# Apollo4-BluePlus-Module_rev_a-v33.net
KiCad netlist of a schematic drawn in EAGLE
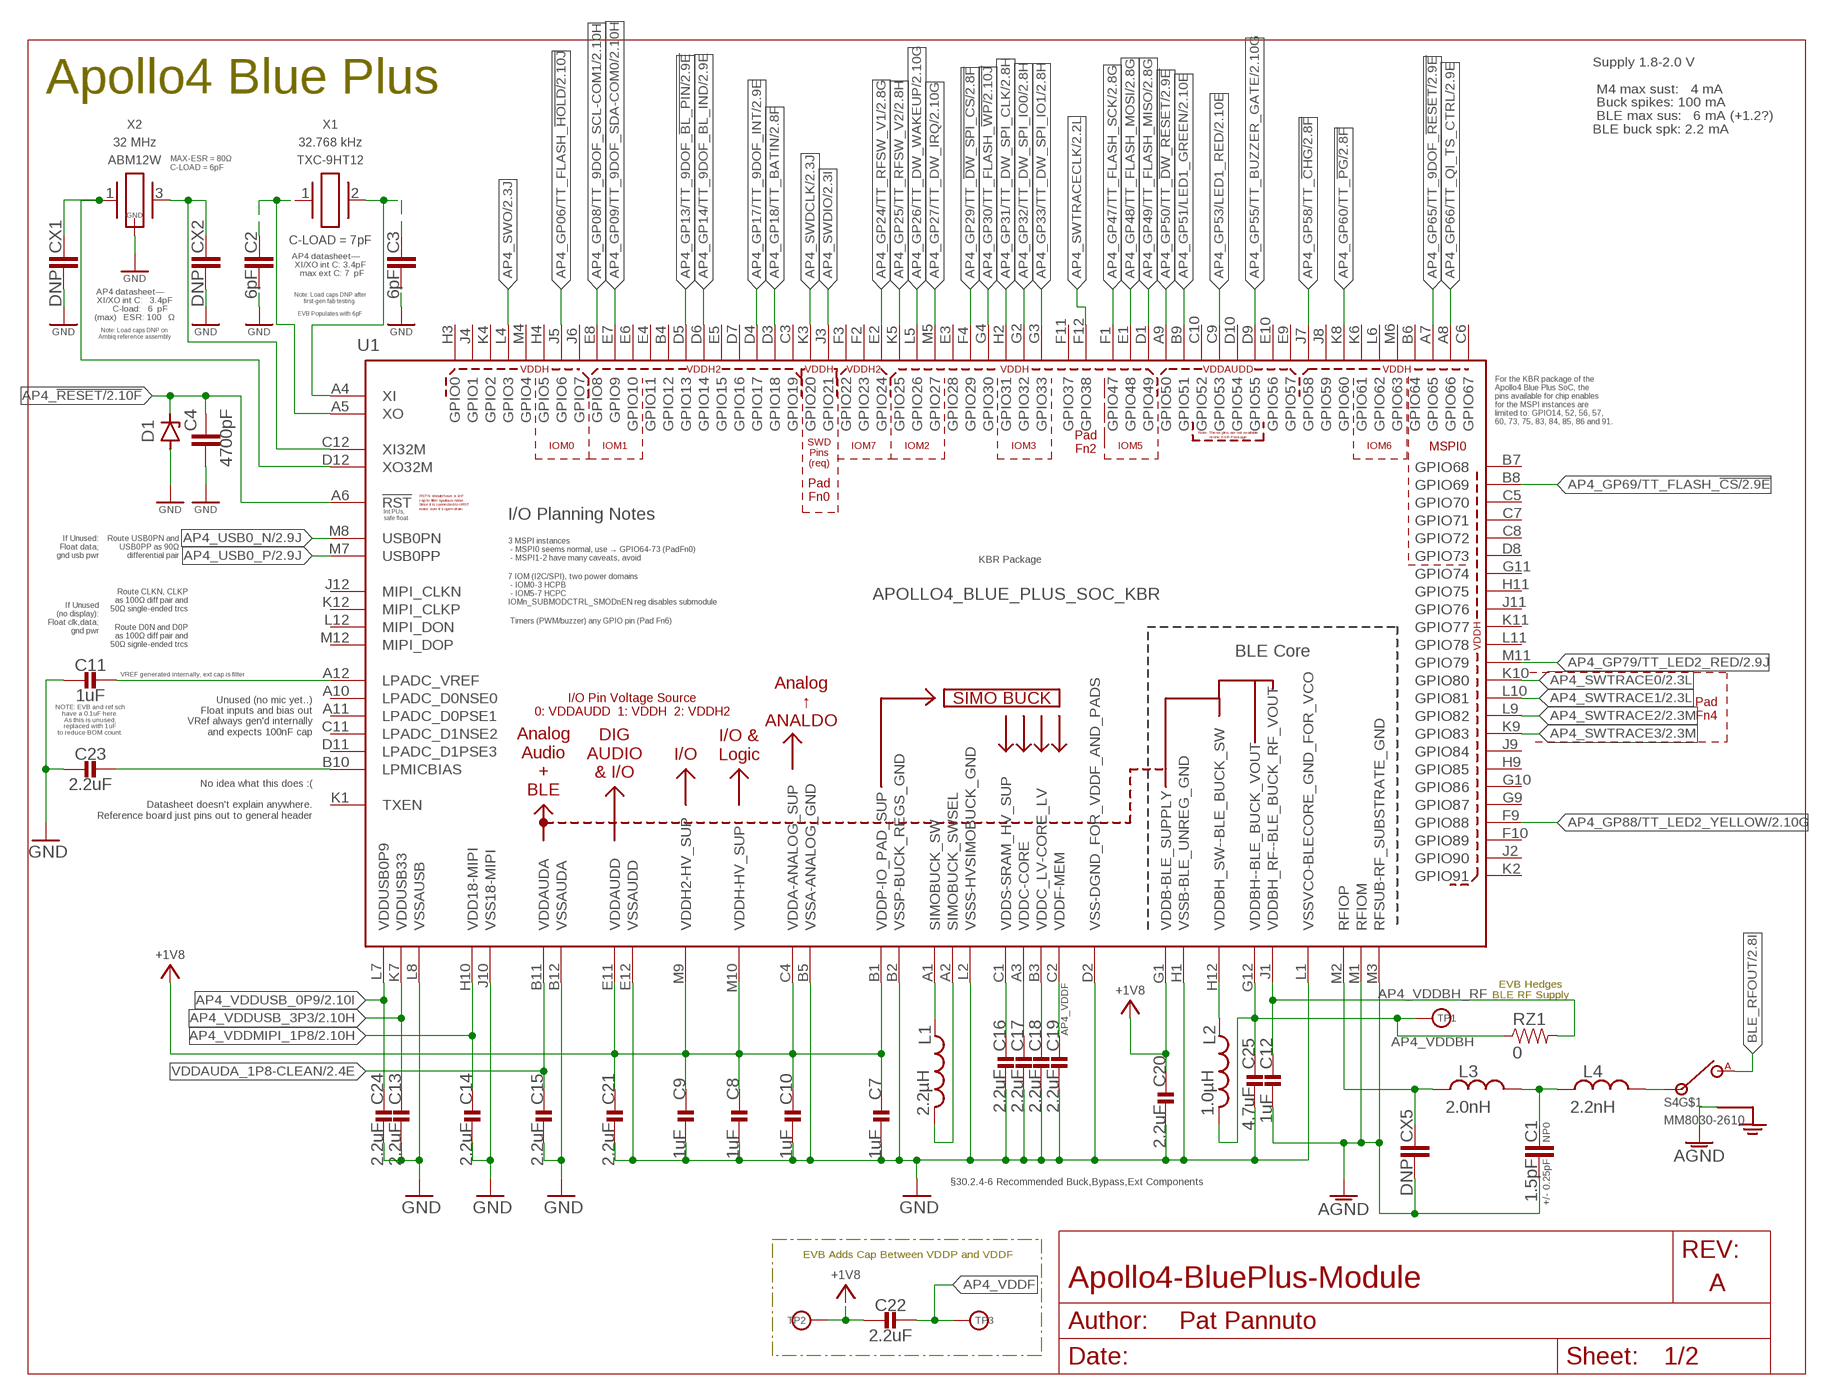
[diagram p0: schematic, sheet 1]
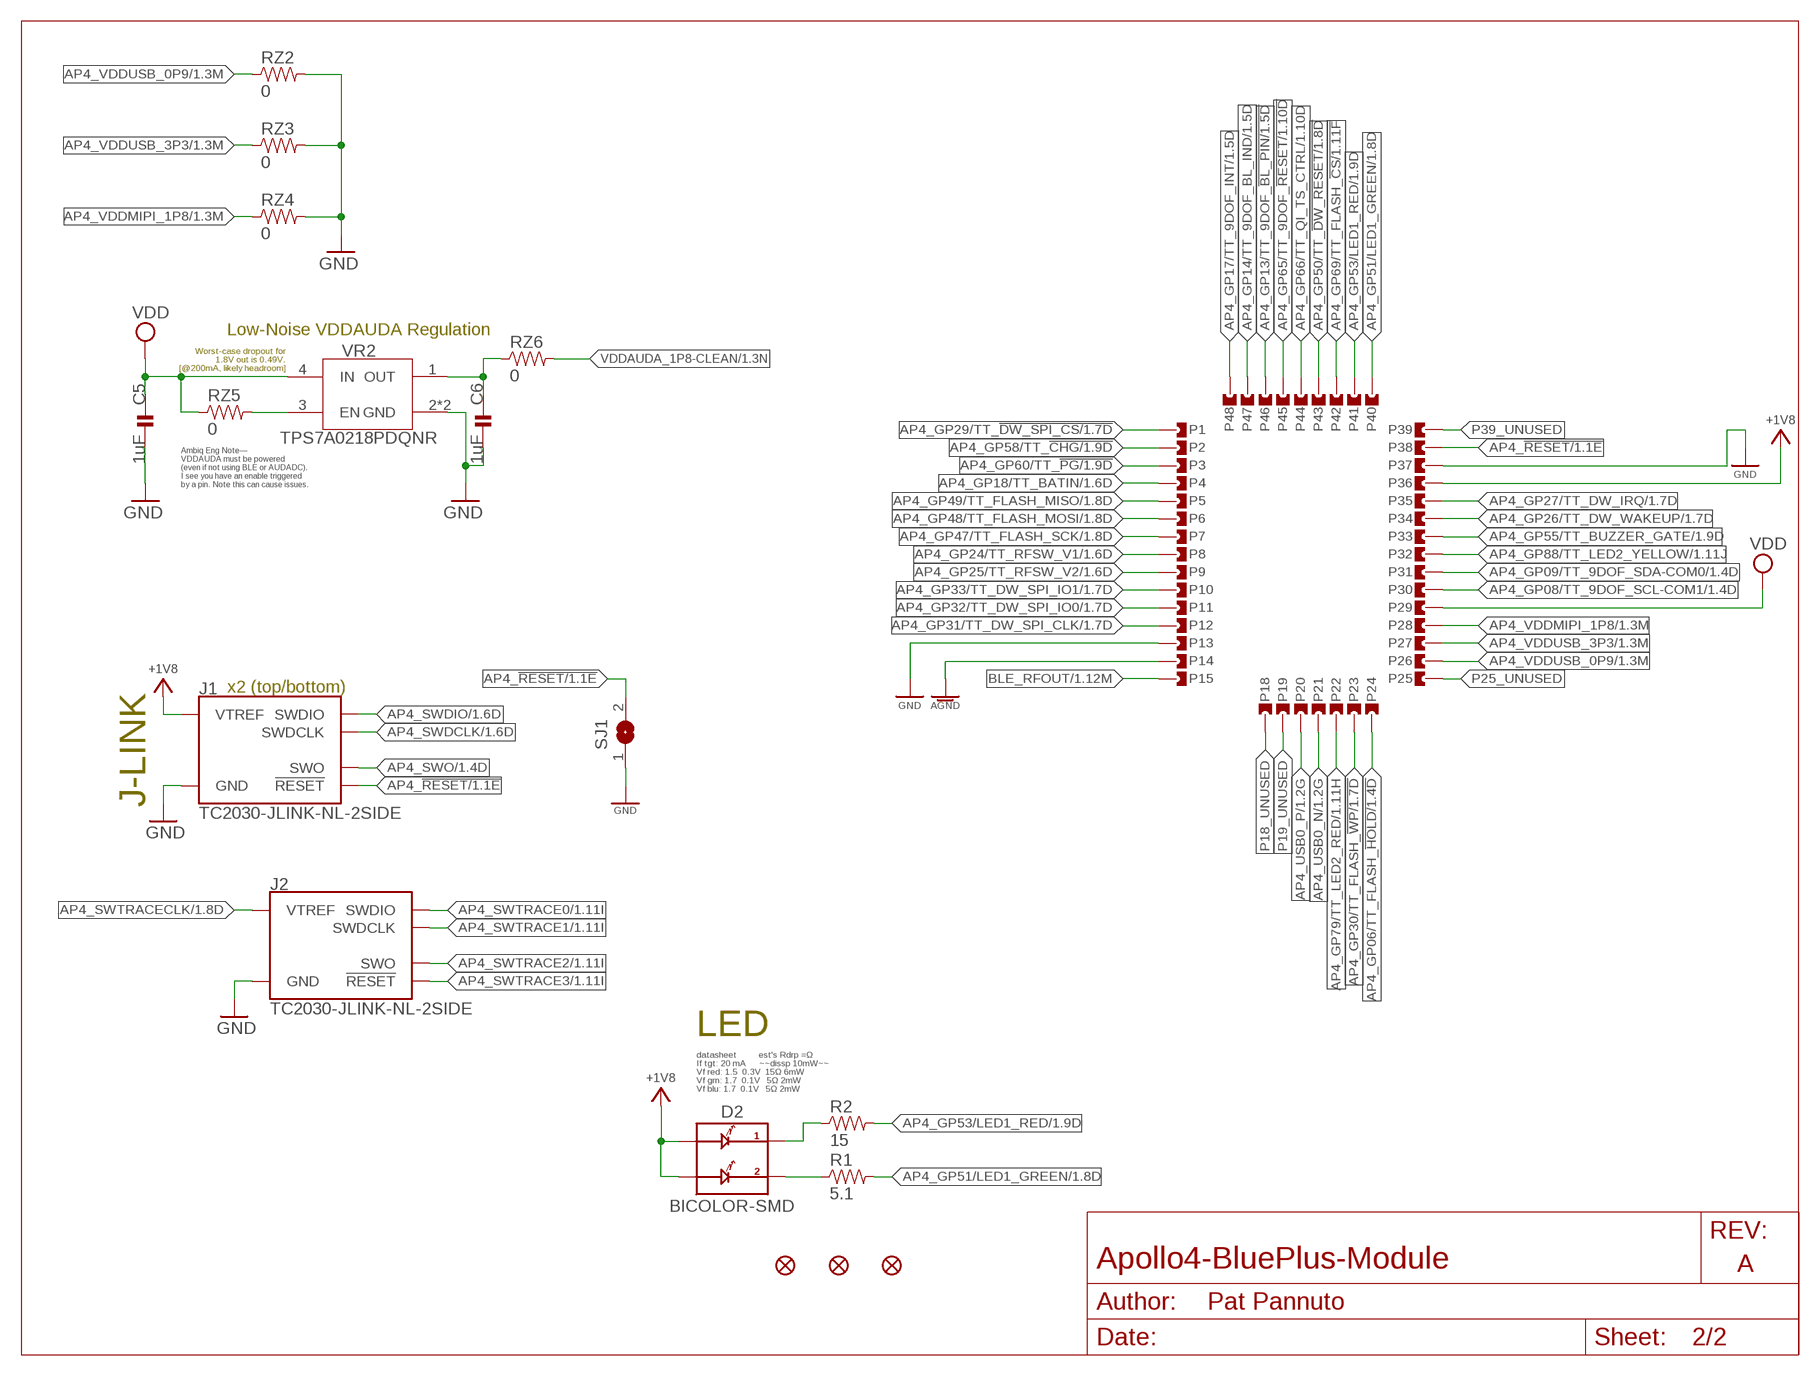
[diagram p1: schematic, sheet 2]

(export (version "E")
  (design (tool "Eeschema 10.0.6"))
  (components
    (comp (ref "C1")
      (value "1.5pF")
      (footprint "eagle-import:CAPC1005X60")
      (description "CAP CER 1.5PF 50V C0G/NP0 0402")
      (fields
        (field (name "MANUFACTURER") "KEMET")
        (field (name "MPN") "C0402C159C5GAC7867")
        (field (name "TEMPCOEFF") "NP0")
        (field (name "TOLERANCE") "+/- 0.25pF")
      )
      (libsource (lib "eagle-import") (part "CCHIP-0402(1005-METRIC)_"))
    )
    (comp (ref "C2")
      (value "6pF")
      (footprint "eagle-import:CAPC1005X60")
      (fields (field (name "MANUFACTURER") "Murata") (field (name "MPN") "GCM1555C1H6R0BA16D"))
      (libsource (lib "eagle-import") (part "CCHIP-0402(1005-METRIC)_"))
    )
    (comp (ref "C3")
      (value "6pF")
      (footprint "eagle-import:CAPC1005X60")
      (fields (field (name "MANUFACTURER") "Murata") (field (name "MPN") "GCM1555C1H6R0BA16D"))
      (libsource (lib "eagle-import") (part "CCHIP-0402(1005-METRIC)_"))
    )
    (comp (ref "C4")
      (value "4700pF")
      (footprint "eagle-import:CAPC1005X60")
      (fields (field (name "MPN") "KGM05AR71E472KH"))
      (libsource (lib "eagle-import") (part "CCHIP-0402(1005-METRIC)_"))
    )
    (comp (ref "C7")
      (value "1uF")
      (footprint "eagle-import:0201_CAP")
      (fields (field (name "MANUFACTURER") "Murata") (field (name "MPN") "GRM033R61A105ME44D"))
      (libsource (lib "eagle-import") (part "passives_20904581_CAPACITOR0201_CAP"))
    )
    (comp (ref "C8")
      (value "1uF")
      (footprint "eagle-import:0201_CAP")
      (fields (field (name "MANUFACTURER") "Murata") (field (name "MPN") "GRM033R61A105ME44D"))
      (libsource (lib "eagle-import") (part "passives_20904581_CAPACITOR0201_CAP"))
    )
    (comp (ref "C9")
      (value "1uF")
      (footprint "eagle-import:0201_CAP")
      (fields (field (name "MANUFACTURER") "Murata") (field (name "MPN") "GRM033R61A105ME44D"))
      (libsource (lib "eagle-import") (part "passives_20904581_CAPACITOR0201_CAP"))
    )
    (comp (ref "C10")
      (value "1uF")
      (footprint "eagle-import:0201_CAP")
      (fields (field (name "MANUFACTURER") "Murata") (field (name "MPN") "GRM033R61A105ME44D"))
      (libsource (lib "eagle-import") (part "passives_20904581_CAPACITOR0201_CAP"))
    )
    (comp (ref "C11")
      (value "1uF")
      (footprint "eagle-import:0201_CAP")
      (fields (field (name "MANUFACTURER") "MURATA") (field (name "MPN") "GRM033R61A105ME44D"))
      (libsource (lib "eagle-import") (part "passives_20904581_CAPACITOR0201_CAP"))
    )
    (comp (ref "C12")
      (value "1uF")
      (footprint "eagle-import:0201_CAP")
      (fields (field (name "MANUFACTURER") "Murata") (field (name "MPN") "GRM033R61A105ME44D"))
      (libsource (lib "eagle-import") (part "passives_20904581_CAPACITOR0201_CAP"))
    )
    (comp (ref "C13")
      (value "2.2uF")
      (footprint "eagle-import:0201_CAP")
      (fields (field (name "MANUFACTURER") "Murata") (field (name "MPN") "GRM033R61A225KE47D"))
      (libsource (lib "eagle-import") (part "passives_20904581_CAPACITOR0201_CAP"))
    )
    (comp (ref "C14")
      (value "2.2uF")
      (footprint "eagle-import:0201_CAP")
      (fields (field (name "MANUFACTURER") "Murata") (field (name "MPN") "GRM033R61A225KE47D"))
      (libsource (lib "eagle-import") (part "passives_20904581_CAPACITOR0201_CAP"))
    )
    (comp (ref "C15")
      (value "2.2uF")
      (footprint "eagle-import:0201_CAP")
      (fields (field (name "MANUFACTURER") "Murata") (field (name "MPN") "GRM033R61A225KE47D"))
      (libsource (lib "eagle-import") (part "passives_20904581_CAPACITOR0201_CAP"))
    )
    (comp (ref "C16")
      (value "2.2uF")
      (footprint "eagle-import:0201_CAP")
      (fields (field (name "MANUFACTURER") "Murata") (field (name "MPN") "GRM033R61A225KE47D"))
      (libsource (lib "eagle-import") (part "passives_20904581_CAPACITOR0201_CAP"))
    )
    (comp (ref "C17")
      (value "2.2uF")
      (footprint "eagle-import:0201_CAP")
      (fields (field (name "MANUFACTURER") "Murata") (field (name "MPN") "GRM033R61A225KE47D"))
      (libsource (lib "eagle-import") (part "passives_20904581_CAPACITOR0201_CAP"))
    )
    (comp (ref "C18")
      (value "2.2uF")
      (footprint "eagle-import:0201_CAP")
      (fields (field (name "MANUFACTURER") "Murata") (field (name "MPN") "GRM033R61A225KE47D"))
      (libsource (lib "eagle-import") (part "passives_20904581_CAPACITOR0201_CAP"))
    )
    (comp (ref "C19")
      (value "2.2uF")
      (footprint "eagle-import:0201_CAP")
      (fields (field (name "MANUFACTURER") "Murata") (field (name "MPN") "GRM033R61A225KE47D"))
      (libsource (lib "eagle-import") (part "passives_20904581_CAPACITOR0201_CAP"))
    )
    (comp (ref "C20")
      (value "2.2uF")
      (footprint "eagle-import:0201_CAP")
      (fields (field (name "MANUFACTURER") "Murata") (field (name "MPN") "GRM033R61A225KE47D"))
      (libsource (lib "eagle-import") (part "passives_20904581_CAPACITOR0201_CAP"))
    )
    (comp (ref "C21")
      (value "2.2uF")
      (footprint "eagle-import:0201_CAP")
      (fields (field (name "MANUFACTURER") "Murata") (field (name "MPN") "GRM033R61A225KE47D"))
      (libsource (lib "eagle-import") (part "passives_20904581_CAPACITOR0201_CAP"))
    )
    (comp (ref "C22")
      (value "2.2uF")
      (footprint "eagle-import:0201_CAP")
      (fields (field (name "MANUFACTURER") "Murata") (field (name "MPN") "GRM033R61A225KE47D"))
      (libsource (lib "eagle-import") (part "passives_20904581_CAPACITOR0201_CAP"))
    )
    (comp (ref "C23")
      (value "2.2uF")
      (footprint "eagle-import:0201_CAP")
      (fields (field (name "MANUFACTURER") "Murata") (field (name "MPN") "GRM033R61A225KE47D"))
      (libsource (lib "eagle-import") (part "passives_20904581_CAPACITOR0201_CAP"))
    )
    (comp (ref "C24")
      (value "2.2uF")
      (footprint "eagle-import:0201_CAP")
      (fields (field (name "MANUFACTURER") "Murata") (field (name "MPN") "GRM033R61A225KE47D"))
      (libsource (lib "eagle-import") (part "passives_20904581_CAPACITOR0201_CAP"))
    )
    (comp (ref "C25")
      (value "4.7uF")
      (footprint "eagle-import:0402_CAP")
      (fields (field (name "MPN") "CL05A475MP5NRNC"))
      (libsource (lib "eagle-import") (part "CAPACITOR0402_CAP"))
    )
    (comp (ref "CX1")
      (value "DNP")
      (footprint "eagle-import:CAPC1005X60")
      (libsource (lib "eagle-import") (part "CCHIP-0402(1005-METRIC)_"))
    )
    (comp (ref "CX2")
      (value "DNP")
      (footprint "eagle-import:CAPC1005X60")
      (libsource (lib "eagle-import") (part "CCHIP-0402(1005-METRIC)_"))
    )
    (comp (ref "CX5")
      (value "DNP")
      (footprint "eagle-import:CAPC1005X60")
      (libsource (lib "eagle-import") (part "CCHIP-0402(1005-METRIC)_"))
    )
    (comp (ref "D1")
      (value "ZENER")
      (footprint "eagle-import:SODFL1608X70")
      (description "DIODE TVS 5.5V STANDOFF 8V BREAKDOWN SC79")
      (fields (field (name "MANUFACTURER") "NXP SEMICONDUCTOR") (field (name "MPN") "PESD5V0X1UB,135"))
      (libsource (lib "eagle-import") (part "ZENERSODFL(1608-METRIC)_"))
    )
    (comp (ref "L1")
      (value "2.2µH")
      (footprint "eagle-import:0805_CAP")
      (fields (field (name "MANUFACTURER") "Murata") (field (name "MPN") "DFE201210U-2R2M=P2"))
      (libsource (lib "eagle-import") (part "INDUCTOR0805"))
    )
    (comp (ref "L2")
      (value "1.0µH")
      (footprint "eagle-import:0603_CAP")
      (fields (field (name "MANUFACTURER") "Murata") (field (name "MPN") "DFE18SAN1R0ME0L"))
      (libsource (lib "eagle-import") (part "INDUCTOR0603"))
    )
    (comp (ref "L3")
      (value "2.0nH")
      (footprint "eagle-import:INDC1006X60N")
      (description "FIXED IND 2.0NH0.1NH SMD")
      (fields
        (field (name "MANUFACTURER") "Central Technologies")
        (field (name "MPN") "CTTF0402F-2N0B")
        (field (name "TOLERANCE") "+/- 0.1 nH")
      )
      (libsource (lib "eagle-import") (part "LCHIP-0402(1006-METRIC)_"))
    )
    (comp (ref "L4")
      (value "2.2nH")
      (footprint "eagle-import:INDC1006X60N")
      (description "FIXED IND 2.2NH0.1NH SMD")
      (fields
        (field (name "MANUFACTURER") "Central Technologies")
        (field (name "MPN") "CTTF0402F-2N2B")
        (field (name "TOLERANCE") "+/- 0.1 nH")
      )
      (libsource (lib "eagle-import") (part "LCHIP-0402(1006-METRIC)_"))
    )
    (comp (ref "RZ1")
      (value "0")
      (footprint "eagle-import:0402_RES")
      (fields (field (name "MPN") "RMCF0402ZT0R00"))
      (libsource (lib "eagle-import") (part "RESISTOR0402_RES"))
    )
    (comp (ref "S4")
      (value "MM8030-2610")
      (footprint "eagle-import:MM8030-2610")
      (fields (field (name "MANUFACTURER") "Murata"))
      (libsource (lib "eagle-import") (part "MM8030-2610"))
    )
    (comp (ref "TP1")
      (value "VDDBH")
      (footprint "eagle-import:PAD.03X.03")
      (libsource (lib "eagle-import") (part "TEST-POINT"))
    )
    (comp (ref "TP2")
      (value "VDDP")
      (footprint "eagle-import:PAD.03X.03")
      (libsource (lib "eagle-import") (part "TEST-POINT"))
    )
    (comp (ref "TP3")
      (value "VDDF")
      (footprint "eagle-import:PAD.03X.03")
      (libsource (lib "eagle-import") (part "TEST-POINT"))
    )
    (comp (ref "U1")
      (value "APOLLO4_BLUE_PLUS_SOC_KBR")
      (footprint "eagle-import:APOLLO4_BLUE_SOC_BGA")
      (libsource (lib "eagle-import") (part "APOLLO4_BLUE_PLUS_SOC_KBR"))
    )
    (comp (ref "X1")
      (value "TXC-9HT12")
      (footprint "eagle-import:TXC-9HT12")
      (fields
        (field (name "C-LOAD") "7pF")
        (field (name "FREQUENCY") "32.768 kHz")
        (field (name "MANUFACTURER") "TXC Corp")
        (field (name "MPN") "9HT12-32.768KDZY-T")
      )
      (libsource (lib "eagle-import") (part "TXC-9HT12"))
    )
    (comp (ref "X2")
      (value "ABM12W")
      (footprint "eagle-import:ABM12W")
      (fields
        (field (name "C-LOAD") "6pF")
        (field (name "FREQUENCY") "32 MHz")
        (field (name "MANUFACTURER") "Abracon")
        (field (name "MAX-ESR") "80Ω")
        (field (name "MPN") "ABM12W-32.0000MHZ-6-D1X-T3")
      )
      (libsource (lib "eagle-import") (part "ABM12W"))
    )
    (comp (ref "C5")
      (value "1uF")
      (footprint "eagle-import:0201_CAP")
      (fields (field (name "MANUFACTURER") "Murata") (field (name "MPN") "GRM033R61A105ME44D"))
      (libsource (lib "eagle-import") (part "passives_20904581_CAPACITOR0201_CAP"))
    )
    (comp (ref "C6")
      (value "1uF")
      (footprint "eagle-import:0201_CAP")
      (fields (field (name "MANUFACTURER") "Murata") (field (name "MPN") "GRM033R61A105ME44D"))
      (libsource (lib "eagle-import") (part "passives_20904581_CAPACITOR0201_CAP"))
    )
    (comp (ref "D2")
      (value "BICOLOR-SMD")
      (footprint "eagle-import:LED-0606")
      (fields (field (name "MPN") "MCL0606FRD1GR1T"))
      (libsource (lib "eagle-import") (part "BICOLOR-SMD"))
    )
    (comp (ref "FD1")
      (value "FIDUCIALUFIDUCIAL")
      (footprint "eagle-import:FIDUCIAL-MICRO")
      (libsource (lib "eagle-import") (part "FIDUCIALUFIDUCIAL"))
    )
    (comp (ref "FD2")
      (value "FIDUCIALUFIDUCIAL")
      (footprint "eagle-import:FIDUCIAL-MICRO")
      (libsource (lib "eagle-import") (part "FIDUCIALUFIDUCIAL"))
    )
    (comp (ref "FD3")
      (value "FIDUCIALUFIDUCIAL")
      (footprint "eagle-import:FIDUCIAL-MICRO")
      (libsource (lib "eagle-import") (part "FIDUCIALUFIDUCIAL"))
    )
    (comp (ref "J1")
      (value "TC2030-JLINK-NL-2SIDE")
      (footprint "eagle-import:TC2030-IDC-NL-2SIDE")
      (libsource (lib "eagle-import") (part "TC2030-JLINK-NL-2SIDE"))
    )
    (comp (ref "J2")
      (value "TC2030-JLINK-NL-2SIDE")
      (footprint "eagle-import:TC2030-IDC-NL-2SIDE")
      (libsource (lib "eagle-import") (part "TC2030-JLINK-NL-2SIDE"))
    )
    (comp (ref "P1")
      (value "CASTELLATION4L")
      (footprint "eagle-import:CASTELLATION-0.55MM_DRILL-4L")
      (libsource (lib "eagle-import") (part "CASTELLATION4L"))
    )
    (comp (ref "P2")
      (value "CASTELLATION4L")
      (footprint "eagle-import:CASTELLATION-0.55MM_DRILL-4L")
      (libsource (lib "eagle-import") (part "CASTELLATION4L"))
    )
    (comp (ref "P3")
      (value "CASTELLATION4L")
      (footprint "eagle-import:CASTELLATION-0.55MM_DRILL-4L")
      (libsource (lib "eagle-import") (part "CASTELLATION4L"))
    )
    (comp (ref "P4")
      (value "CASTELLATION4L")
      (footprint "eagle-import:CASTELLATION-0.55MM_DRILL-4L")
      (libsource (lib "eagle-import") (part "CASTELLATION4L"))
    )
    (comp (ref "P5")
      (value "CASTELLATION4L")
      (footprint "eagle-import:CASTELLATION-0.55MM_DRILL-4L")
      (libsource (lib "eagle-import") (part "CASTELLATION4L"))
    )
    (comp (ref "P6")
      (value "CASTELLATION4L")
      (footprint "eagle-import:CASTELLATION-0.55MM_DRILL-4L")
      (libsource (lib "eagle-import") (part "CASTELLATION4L"))
    )
    (comp (ref "P7")
      (value "CASTELLATION4L")
      (footprint "eagle-import:CASTELLATION-0.55MM_DRILL-4L")
      (libsource (lib "eagle-import") (part "CASTELLATION4L"))
    )
    (comp (ref "P8")
      (value "CASTELLATION4L")
      (footprint "eagle-import:CASTELLATION-0.55MM_DRILL-4L")
      (libsource (lib "eagle-import") (part "CASTELLATION4L"))
    )
    (comp (ref "P9")
      (value "CASTELLATION4L")
      (footprint "eagle-import:CASTELLATION-0.55MM_DRILL-4L")
      (libsource (lib "eagle-import") (part "CASTELLATION4L"))
    )
    (comp (ref "P10")
      (value "CASTELLATION4L")
      (footprint "eagle-import:CASTELLATION-0.55MM_DRILL-4L")
      (libsource (lib "eagle-import") (part "CASTELLATION4L"))
    )
    (comp (ref "P11")
      (value "CASTELLATION4L")
      (footprint "eagle-import:CASTELLATION-0.55MM_DRILL-4L")
      (libsource (lib "eagle-import") (part "CASTELLATION4L"))
    )
    (comp (ref "P12")
      (value "CASTELLATION4L")
      (footprint "eagle-import:CASTELLATION-0.55MM_DRILL-4L")
      (libsource (lib "eagle-import") (part "CASTELLATION4L"))
    )
    (comp (ref "P13")
      (value "CASTELLATION4L")
      (footprint "eagle-import:CASTELLATION-0.55MM_DRILL-4L")
      (libsource (lib "eagle-import") (part "CASTELLATION4L"))
    )
    (comp (ref "P14")
      (value "CASTELLATION4L")
      (footprint "eagle-import:CASTELLATION-0.55MM_DRILL-4L")
      (libsource (lib "eagle-import") (part "CASTELLATION4L"))
    )
    (comp (ref "P15")
      (value "CASTELLATION4L")
      (footprint "eagle-import:CASTELLATION-0.55MM_DRILL-4L")
      (libsource (lib "eagle-import") (part "CASTELLATION4L"))
    )
    (comp (ref "P18")
      (value "CASTELLATION4L")
      (footprint "eagle-import:CASTELLATION-0.55MM_DRILL-4L")
      (libsource (lib "eagle-import") (part "CASTELLATION4L"))
    )
    (comp (ref "P19")
      (value "CASTELLATION4L")
      (footprint "eagle-import:CASTELLATION-0.55MM_DRILL-4L")
      (libsource (lib "eagle-import") (part "CASTELLATION4L"))
    )
    (comp (ref "P20")
      (value "CASTELLATION4L")
      (footprint "eagle-import:CASTELLATION-0.55MM_DRILL-4L")
      (libsource (lib "eagle-import") (part "CASTELLATION4L"))
    )
    (comp (ref "P21")
      (value "CASTELLATION4L")
      (footprint "eagle-import:CASTELLATION-0.55MM_DRILL-4L")
      (libsource (lib "eagle-import") (part "CASTELLATION4L"))
    )
    (comp (ref "P22")
      (value "CASTELLATION4L")
      (footprint "eagle-import:CASTELLATION-0.55MM_DRILL-4L")
      (libsource (lib "eagle-import") (part "CASTELLATION4L"))
    )
    (comp (ref "P23")
      (value "CASTELLATION4L")
      (footprint "eagle-import:CASTELLATION-0.55MM_DRILL-4L")
      (libsource (lib "eagle-import") (part "CASTELLATION4L"))
    )
    (comp (ref "P24")
      (value "CASTELLATION4L")
      (footprint "eagle-import:CASTELLATION-0.55MM_DRILL-4L")
      (libsource (lib "eagle-import") (part "CASTELLATION4L"))
    )
    (comp (ref "P25")
      (value "CASTELLATION4L")
      (footprint "eagle-import:CASTELLATION-0.55MM_DRILL-4L")
      (libsource (lib "eagle-import") (part "CASTELLATION4L"))
    )
    (comp (ref "P26")
      (value "CASTELLATION4L")
      (footprint "eagle-import:CASTELLATION-0.55MM_DRILL-4L")
      (libsource (lib "eagle-import") (part "CASTELLATION4L"))
    )
    (comp (ref "P27")
      (value "CASTELLATION4L")
      (footprint "eagle-import:CASTELLATION-0.55MM_DRILL-4L")
      (libsource (lib "eagle-import") (part "CASTELLATION4L"))
    )
    (comp (ref "P28")
      (value "CASTELLATION4L")
      (footprint "eagle-import:CASTELLATION-0.55MM_DRILL-4L")
      (libsource (lib "eagle-import") (part "CASTELLATION4L"))
    )
    (comp (ref "P29")
      (value "CASTELLATION4L")
      (footprint "eagle-import:CASTELLATION-0.55MM_DRILL-4L")
      (libsource (lib "eagle-import") (part "CASTELLATION4L"))
    )
    (comp (ref "P30")
      (value "CASTELLATION4L")
      (footprint "eagle-import:CASTELLATION-0.55MM_DRILL-4L")
      (libsource (lib "eagle-import") (part "CASTELLATION4L"))
    )
    (comp (ref "P31")
      (value "CASTELLATION4L")
      (footprint "eagle-import:CASTELLATION-0.55MM_DRILL-4L")
      (libsource (lib "eagle-import") (part "CASTELLATION4L"))
    )
    (comp (ref "P32")
      (value "CASTELLATION4L")
      (footprint "eagle-import:CASTELLATION-0.55MM_DRILL-4L")
      (libsource (lib "eagle-import") (part "CASTELLATION4L"))
    )
    (comp (ref "P33")
      (value "CASTELLATION4L")
      (footprint "eagle-import:CASTELLATION-0.55MM_DRILL-4L")
      (libsource (lib "eagle-import") (part "CASTELLATION4L"))
    )
    (comp (ref "P34")
      (value "CASTELLATION4L")
      (footprint "eagle-import:CASTELLATION-0.55MM_DRILL-4L")
      (libsource (lib "eagle-import") (part "CASTELLATION4L"))
    )
    (comp (ref "P35")
      (value "CASTELLATION4L")
      (footprint "eagle-import:CASTELLATION-0.55MM_DRILL-4L")
      (libsource (lib "eagle-import") (part "CASTELLATION4L"))
    )
    (comp (ref "P36")
      (value "CASTELLATION4L")
      (footprint "eagle-import:CASTELLATION-0.55MM_DRILL-4L")
      (libsource (lib "eagle-import") (part "CASTELLATION4L"))
    )
    (comp (ref "P37")
      (value "CASTELLATION4L")
      (footprint "eagle-import:CASTELLATION-0.55MM_DRILL-4L")
      (libsource (lib "eagle-import") (part "CASTELLATION4L"))
    )
    (comp (ref "P38")
      (value "CASTELLATION4L")
      (footprint "eagle-import:CASTELLATION-0.55MM_DRILL-4L")
      (libsource (lib "eagle-import") (part "CASTELLATION4L"))
    )
    (comp (ref "P39")
      (value "CASTELLATION4L")
      (footprint "eagle-import:CASTELLATION-0.55MM_DRILL-4L")
      (libsource (lib "eagle-import") (part "CASTELLATION4L"))
    )
    (comp (ref "P40")
      (value "CASTELLATION4L")
      (footprint "eagle-import:CASTELLATION-0.55MM_DRILL-4L")
      (libsource (lib "eagle-import") (part "CASTELLATION4L"))
    )
    (comp (ref "P41")
      (value "CASTELLATION4L")
      (footprint "eagle-import:CASTELLATION-0.55MM_DRILL-4L")
      (libsource (lib "eagle-import") (part "CASTELLATION4L"))
    )
    (comp (ref "P42")
      (value "CASTELLATION4L")
      (footprint "eagle-import:CASTELLATION-0.55MM_DRILL-4L")
      (libsource (lib "eagle-import") (part "CASTELLATION4L"))
    )
    (comp (ref "P43")
      (value "CASTELLATION4L")
      (footprint "eagle-import:CASTELLATION-0.55MM_DRILL-4L")
      (libsource (lib "eagle-import") (part "CASTELLATION4L"))
    )
    (comp (ref "P44")
      (value "CASTELLATION4L")
      (footprint "eagle-import:CASTELLATION-0.55MM_DRILL-4L")
      (libsource (lib "eagle-import") (part "CASTELLATION4L"))
    )
    (comp (ref "P45")
      (value "CASTELLATION4L")
      (footprint "eagle-import:CASTELLATION-0.55MM_DRILL-4L")
      (libsource (lib "eagle-import") (part "CASTELLATION4L"))
    )
    (comp (ref "P46")
      (value "CASTELLATION4L")
      (footprint "eagle-import:CASTELLATION-0.55MM_DRILL-4L")
      (libsource (lib "eagle-import") (part "CASTELLATION4L"))
    )
    (comp (ref "P47")
      (value "CASTELLATION4L")
      (footprint "eagle-import:CASTELLATION-0.55MM_DRILL-4L")
      (libsource (lib "eagle-import") (part "CASTELLATION4L"))
    )
    (comp (ref "P48")
      (value "CASTELLATION4L")
      (footprint "eagle-import:CASTELLATION-0.55MM_DRILL-4L")
      (libsource (lib "eagle-import") (part "CASTELLATION4L"))
    )
    (comp (ref "R1")
      (value "5.1")
      (footprint "eagle-import:0201_RES")
      (fields (field (name "MPN") "SR731HTTC5R10F"))
      (libsource (lib "eagle-import") (part "RESISTOR0201_RES"))
    )
    (comp (ref "R2")
      (value "15")
      (footprint "eagle-import:0201_RES")
      (description "RES SMD 15 OHM 5% 1/20W 0201")
      (fields (field (name "MPN") "ERJ-1GNJ150C"))
      (libsource (lib "eagle-import") (part "RESISTOR0201_RES"))
    )
    (comp (ref "RZ2")
      (value "0")
      (footprint "eagle-import:0402_RES")
      (fields (field (name "MPN") "RMCF0402ZT0R00"))
      (libsource (lib "eagle-import") (part "RESISTOR0402_RES"))
    )
    (comp (ref "RZ3")
      (value "0")
      (footprint "eagle-import:0402_RES")
      (fields (field (name "MPN") "RMCF0402ZT0R00"))
      (libsource (lib "eagle-import") (part "RESISTOR0402_RES"))
    )
    (comp (ref "RZ4")
      (value "0")
      (footprint "eagle-import:0402_RES")
      (fields (field (name "MPN") "RMCF0402ZT0R00"))
      (libsource (lib "eagle-import") (part "RESISTOR0402_RES"))
    )
    (comp (ref "RZ5")
      (value "0")
      (footprint "eagle-import:0402_RES")
      (fields (field (name "MPN") "RMCF0402ZT0R00"))
      (libsource (lib "eagle-import") (part "RESISTOR0402_RES"))
    )
    (comp (ref "RZ6")
      (value "0")
      (footprint "eagle-import:0402_RES")
      (fields (field (name "MPN") "RMCF0402ZT0R00"))
      (libsource (lib "eagle-import") (part "RESISTOR0402_RES"))
    )
    (comp (ref "SJ1") (value "SJ") (footprint "eagle-import:SJ") (libsource (lib "eagle-import") (part "SJ")))
    (comp (ref "VR2")
      (value "TPS7A0218PDQNR")
      (footprint "eagle-import:4-XDFN-EP")
      (libsource (lib "eagle-import") (part "TPS7A0218PDQNR"))
    )
  )
  (nets
    (net (code "1") (name "+1V8") (class "Default")
      (node (ref "C10") (pin "P$1") (pinfunction "1_P$1") (pintype "bidirectional"))
      (node (ref "C20") (pin "P$1") (pinfunction "1_P$1") (pintype "bidirectional"))
      (node (ref "C21") (pin "P$1") (pinfunction "1_P$1") (pintype "bidirectional"))
      (node (ref "C22") (pin "P$2") (pinfunction "2_P$2") (pintype "bidirectional"))
      (node (ref "C7") (pin "P$1") (pinfunction "1_P$1") (pintype "bidirectional"))
      (node (ref "C8") (pin "P$1") (pinfunction "1_P$1") (pintype "bidirectional"))
      (node (ref "C9") (pin "P$1") (pinfunction "1_P$1") (pintype "bidirectional"))
      (node (ref "D2") (pin "A1") (pinfunction "A1_A1") (pintype "bidirectional"))
      (node (ref "D2") (pin "A2") (pinfunction "A2_A2") (pintype "bidirectional"))
      (node (ref "J1") (pin "1") (pinfunction "VTREF_1") (pintype "bidirectional"))
      (node (ref "J1") (pin "B1") (pinfunction "VTREF_B1") (pintype "bidirectional"))
      (node (ref "P36") (pin "P$1") (pinfunction "P$1_P$1") (pintype "bidirectional"))
      (node (ref "P36") (pin "P$2") (pinfunction "P$1_P$2") (pintype "bidirectional"))
      (node (ref "P36") (pin "P$3") (pinfunction "P$1_P$3") (pintype "bidirectional"))
      (node (ref "TP2") (pin "P$1") (pinfunction "TESTPOINT_P$1") (pintype "bidirectional"))
      (node (ref "U1") (pin "B1") (pinfunction "VDDP-IO_PAD_SUP_B1") (pintype "bidirectional"))
      (node (ref "U1") (pin "C4") (pinfunction "VDDA-ANALOG_SUP_C4") (pintype "bidirectional"))
      (node (ref "U1") (pin "E11") (pinfunction "VDDAUDD_E11") (pintype "bidirectional"))
      (node (ref "U1") (pin "G1") (pinfunction "VDDB-BLE_SUPPLY_G1") (pintype "bidirectional"))
      (node (ref "U1") (pin "M10") (pinfunction "VDDH-HV_SUP_M10") (pintype "bidirectional"))
      (node (ref "U1") (pin "M9") (pinfunction "VDDH2-HV_SUP_M9") (pintype "bidirectional"))
    )
    (net (code "2") (name "AGND") (class "Default")
      (node (ref "C1") (pin "2") (pinfunction "2_2") (pintype "passive"))
      (node (ref "C12") (pin "P$2") (pinfunction "2_P$2") (pintype "bidirectional"))
      (node (ref "CX5") (pin "2") (pinfunction "2_2") (pintype "passive"))
      (node (ref "P14") (pin "P$1") (pinfunction "P$1_P$1") (pintype "bidirectional"))
      (node (ref "P14") (pin "P$2") (pinfunction "P$1_P$2") (pintype "bidirectional"))
      (node (ref "P14") (pin "P$3") (pinfunction "P$1_P$3") (pintype "bidirectional"))
      (node (ref "S4") (pin "G1") (pinfunction "GND_G1") (pintype "bidirectional"))
      (node (ref "S4") (pin "G2") (pinfunction "GND_G2") (pintype "bidirectional"))
      (node (ref "U1") (pin "M1") (pinfunction "RFIOM_M1") (pintype "bidirectional"))
      (node (ref "U1") (pin "M3") (pinfunction "RFSUB-RF_SUBSTRATE_GND_M3") (pintype "bidirectional"))
    )
    (net (code "3") (name "AP4_GP06{slash}TT_FLASH_~{HOLD}") (class "Default")
      (node (ref "P24") (pin "P$1") (pinfunction "P$1_P$1") (pintype "bidirectional"))
      (node (ref "P24") (pin "P$2") (pinfunction "P$1_P$2") (pintype "bidirectional"))
      (node (ref "P24") (pin "P$3") (pinfunction "P$1_P$3") (pintype "bidirectional"))
      (node (ref "U1") (pin "J5") (pinfunction "GPIO6_J5") (pintype "bidirectional"))
    )
    (net (code "4") (name "AP4_GP08{slash}TT_9DOF_SCL-COM1") (class "Default")
      (node (ref "P30") (pin "P$1") (pinfunction "P$1_P$1") (pintype "bidirectional"))
      (node (ref "P30") (pin "P$2") (pinfunction "P$1_P$2") (pintype "bidirectional"))
      (node (ref "P30") (pin "P$3") (pinfunction "P$1_P$3") (pintype "bidirectional"))
      (node (ref "U1") (pin "E8") (pinfunction "GPIO8_E8") (pintype "bidirectional"))
    )
    (net (code "5") (name "AP4_GP09{slash}TT_9DOF_SDA-COM0") (class "Default")
      (node (ref "P31") (pin "P$1") (pinfunction "P$1_P$1") (pintype "bidirectional"))
      (node (ref "P31") (pin "P$2") (pinfunction "P$1_P$2") (pintype "bidirectional"))
      (node (ref "P31") (pin "P$3") (pinfunction "P$1_P$3") (pintype "bidirectional"))
      (node (ref "U1") (pin "E7") (pinfunction "GPIO9_E7") (pintype "bidirectional"))
    )
    (net (code "6") (name "AP4_GP13{slash}TT_9DOF_~{BL_PIN}") (class "Default")
      (node (ref "P46") (pin "P$1") (pinfunction "P$1_P$1") (pintype "bidirectional"))
      (node (ref "P46") (pin "P$2") (pinfunction "P$1_P$2") (pintype "bidirectional"))
      (node (ref "P46") (pin "P$3") (pinfunction "P$1_P$3") (pintype "bidirectional"))
      (node (ref "U1") (pin "D5") (pinfunction "GPIO13_D5") (pintype "bidirectional"))
    )
    (net (code "7") (name "AP4_GP14{slash}TT_9DOF_BL_IND") (class "Default")
      (node (ref "P47") (pin "P$1") (pinfunction "P$1_P$1") (pintype "bidirectional"))
      (node (ref "P47") (pin "P$2") (pinfunction "P$1_P$2") (pintype "bidirectional"))
      (node (ref "P47") (pin "P$3") (pinfunction "P$1_P$3") (pintype "bidirectional"))
      (node (ref "U1") (pin "D6") (pinfunction "GPIO14_D6") (pintype "bidirectional"))
    )
    (net (code "8") (name "AP4_GP17{slash}TT_9DOF_INT") (class "Default")
      (node (ref "P48") (pin "P$1") (pinfunction "P$1_P$1") (pintype "bidirectional"))
      (node (ref "P48") (pin "P$2") (pinfunction "P$1_P$2") (pintype "bidirectional"))
      (node (ref "P48") (pin "P$3") (pinfunction "P$1_P$3") (pintype "bidirectional"))
      (node (ref "U1") (pin "D4") (pinfunction "GPIO17_D4") (pintype "bidirectional"))
    )
    (net (code "9") (name "AP4_GP18{slash}TT_BATIN") (class "Default")
      (node (ref "P4") (pin "P$1") (pinfunction "P$1_P$1") (pintype "bidirectional"))
      (node (ref "P4") (pin "P$2") (pinfunction "P$1_P$2") (pintype "bidirectional"))
      (node (ref "P4") (pin "P$3") (pinfunction "P$1_P$3") (pintype "bidirectional"))
      (node (ref "U1") (pin "D3") (pinfunction "GPIO18_D3") (pintype "bidirectional"))
    )
    (net (code "10") (name "AP4_GP24{slash}TT_RFSW_V1") (class "Default")
      (node (ref "P8") (pin "P$1") (pinfunction "P$1_P$1") (pintype "bidirectional"))
      (node (ref "P8") (pin "P$2") (pinfunction "P$1_P$2") (pintype "bidirectional"))
      (node (ref "P8") (pin "P$3") (pinfunction "P$1_P$3") (pintype "bidirectional"))
      (node (ref "U1") (pin "E2") (pinfunction "GPIO24_E2") (pintype "bidirectional"))
    )
    (net (code "11") (name "AP4_GP25{slash}TT_RFSW_V2") (class "Default")
      (node (ref "P9") (pin "P$1") (pinfunction "P$1_P$1") (pintype "bidirectional"))
      (node (ref "P9") (pin "P$2") (pinfunction "P$1_P$2") (pintype "bidirectional"))
      (node (ref "P9") (pin "P$3") (pinfunction "P$1_P$3") (pintype "bidirectional"))
      (node (ref "U1") (pin "K5") (pinfunction "GPIO25_K5") (pintype "bidirectional"))
    )
    (net (code "12") (name "AP4_GP26{slash}TT_DW_WAKEUP") (class "Default")
      (node (ref "P34") (pin "P$1") (pinfunction "P$1_P$1") (pintype "bidirectional"))
      (node (ref "P34") (pin "P$2") (pinfunction "P$1_P$2") (pintype "bidirectional"))
      (node (ref "P34") (pin "P$3") (pinfunction "P$1_P$3") (pintype "bidirectional"))
      (node (ref "U1") (pin "L5") (pinfunction "GPIO26_L5") (pintype "bidirectional"))
    )
    (net (code "13") (name "AP4_GP27{slash}TT_DW_IRQ") (class "Default")
      (node (ref "P35") (pin "P$1") (pinfunction "P$1_P$1") (pintype "bidirectional"))
      (node (ref "P35") (pin "P$2") (pinfunction "P$1_P$2") (pintype "bidirectional"))
      (node (ref "P35") (pin "P$3") (pinfunction "P$1_P$3") (pintype "bidirectional"))
      (node (ref "U1") (pin "M5") (pinfunction "GPIO27_M5") (pintype "bidirectional"))
    )
    (net (code "14") (name "AP4_GP29{slash}TT_~{DW_SPI_CS}") (class "Default")
      (node (ref "P1") (pin "P$1") (pinfunction "P$1_P$1") (pintype "bidirectional"))
      (node (ref "P1") (pin "P$2") (pinfunction "P$1_P$2") (pintype "bidirectional"))
      (node (ref "P1") (pin "P$3") (pinfunction "P$1_P$3") (pintype "bidirectional"))
      (node (ref "U1") (pin "F4") (pinfunction "GPIO29_F4") (pintype "bidirectional"))
    )
    (net (code "15") (name "AP4_GP30{slash}TT_FLASH_~{WP}") (class "Default")
      (node (ref "P23") (pin "P$1") (pinfunction "P$1_P$1") (pintype "bidirectional"))
      (node (ref "P23") (pin "P$2") (pinfunction "P$1_P$2") (pintype "bidirectional"))
      (node (ref "P23") (pin "P$3") (pinfunction "P$1_P$3") (pintype "bidirectional"))
      (node (ref "U1") (pin "G4") (pinfunction "GPIO30_G4") (pintype "bidirectional"))
    )
    (net (code "16") (name "AP4_GP31{slash}TT_DW_SPI_CLK") (class "Default")
      (node (ref "P12") (pin "P$1") (pinfunction "P$1_P$1") (pintype "bidirectional"))
      (node (ref "P12") (pin "P$2") (pinfunction "P$1_P$2") (pintype "bidirectional"))
      (node (ref "P12") (pin "P$3") (pinfunction "P$1_P$3") (pintype "bidirectional"))
      (node (ref "U1") (pin "H2") (pinfunction "GPIO31_H2") (pintype "bidirectional"))
    )
    (net (code "17") (name "AP4_GP32{slash}TT_DW_SPI_IO0") (class "Default")
      (node (ref "P11") (pin "P$1") (pinfunction "P$1_P$1") (pintype "bidirectional"))
      (node (ref "P11") (pin "P$2") (pinfunction "P$1_P$2") (pintype "bidirectional"))
      (node (ref "P11") (pin "P$3") (pinfunction "P$1_P$3") (pintype "bidirectional"))
      (node (ref "U1") (pin "G2") (pinfunction "GPIO32_G2") (pintype "bidirectional"))
    )
    (net (code "18") (name "AP4_GP33{slash}TT_DW_SPI_IO1") (class "Default")
      (node (ref "P10") (pin "P$1") (pinfunction "P$1_P$1") (pintype "bidirectional"))
      (node (ref "P10") (pin "P$2") (pinfunction "P$1_P$2") (pintype "bidirectional"))
      (node (ref "P10") (pin "P$3") (pinfunction "P$1_P$3") (pintype "bidirectional"))
      (node (ref "U1") (pin "G3") (pinfunction "GPIO33_G3") (pintype "bidirectional"))
    )
    (net (code "19") (name "AP4_GP47{slash}TT_FLASH_SCK") (class "Default")
      (node (ref "P7") (pin "P$1") (pinfunction "P$1_P$1") (pintype "bidirectional"))
      (node (ref "P7") (pin "P$2") (pinfunction "P$1_P$2") (pintype "bidirectional"))
      (node (ref "P7") (pin "P$3") (pinfunction "P$1_P$3") (pintype "bidirectional"))
      (node (ref "U1") (pin "F1") (pinfunction "GPIO47_F1") (pintype "bidirectional"))
    )
    (net (code "20") (name "AP4_GP48{slash}TT_FLASH_MOSI") (class "Default")
      (node (ref "P6") (pin "P$1") (pinfunction "P$1_P$1") (pintype "bidirectional"))
      (node (ref "P6") (pin "P$2") (pinfunction "P$1_P$2") (pintype "bidirectional"))
      (node (ref "P6") (pin "P$3") (pinfunction "P$1_P$3") (pintype "bidirectional"))
      (node (ref "U1") (pin "E1") (pinfunction "GPIO48_E1") (pintype "bidirectional"))
    )
    (net (code "21") (name "AP4_GP49{slash}TT_FLASH_MISO") (class "Default")
      (node (ref "P5") (pin "P$1") (pinfunction "P$1_P$1") (pintype "bidirectional"))
      (node (ref "P5") (pin "P$2") (pinfunction "P$1_P$2") (pintype "bidirectional"))
      (node (ref "P5") (pin "P$3") (pinfunction "P$1_P$3") (pintype "bidirectional"))
      (node (ref "U1") (pin "D1") (pinfunction "GPIO49_D1") (pintype "bidirectional"))
    )
    (net (code "22") (name "AP4_GP50{slash}TT_~{DW_RESET}") (class "Default")
      (node (ref "P43") (pin "P$1") (pinfunction "P$1_P$1") (pintype "bidirectional"))
      (node (ref "P43") (pin "P$2") (pinfunction "P$1_P$2") (pintype "bidirectional"))
      (node (ref "P43") (pin "P$3") (pinfunction "P$1_P$3") (pintype "bidirectional"))
      (node (ref "U1") (pin "A9") (pinfunction "GPIO50_A9") (pintype "bidirectional"))
    )
    (net (code "23") (name "AP4_GP51{slash}LED1_GREEN") (class "Default")
      (node (ref "P40") (pin "P$1") (pinfunction "P$1_P$1") (pintype "bidirectional"))
      (node (ref "P40") (pin "P$2") (pinfunction "P$1_P$2") (pintype "bidirectional"))
      (node (ref "P40") (pin "P$3") (pinfunction "P$1_P$3") (pintype "bidirectional"))
      (node (ref "R1") (pin "2") (pinfunction "2_2") (pintype "passive"))
      (node (ref "U1") (pin "B9") (pinfunction "GPIO51_B9") (pintype "bidirectional"))
    )
    (net (code "24") (name "AP4_GP53{slash}LED1_RED") (class "Default")
      (node (ref "P41") (pin "P$1") (pinfunction "P$1_P$1") (pintype "bidirectional"))
      (node (ref "P41") (pin "P$2") (pinfunction "P$1_P$2") (pintype "bidirectional"))
      (node (ref "P41") (pin "P$3") (pinfunction "P$1_P$3") (pintype "bidirectional"))
      (node (ref "R2") (pin "2") (pinfunction "2_2") (pintype "passive"))
      (node (ref "U1") (pin "C9") (pinfunction "GPIO53_C9") (pintype "bidirectional"))
    )
    (net (code "25") (name "AP4_GP55{slash}TT_BUZZER_GATE") (class "Default")
      (node (ref "P33") (pin "P$1") (pinfunction "P$1_P$1") (pintype "bidirectional"))
      (node (ref "P33") (pin "P$2") (pinfunction "P$1_P$2") (pintype "bidirectional"))
      (node (ref "P33") (pin "P$3") (pinfunction "P$1_P$3") (pintype "bidirectional"))
      (node (ref "U1") (pin "D9") (pinfunction "GPIO55_D9") (pintype "bidirectional"))
    )
    (net (code "26") (name "AP4_GP58{slash}TT_~{CHG}") (class "Default")
      (node (ref "P2") (pin "P$1") (pinfunction "P$1_P$1") (pintype "bidirectional"))
      (node (ref "P2") (pin "P$2") (pinfunction "P$1_P$2") (pintype "bidirectional"))
      (node (ref "P2") (pin "P$3") (pinfunction "P$1_P$3") (pintype "bidirectional"))
      (node (ref "U1") (pin "J7") (pinfunction "GPIO58_J7") (pintype "bidirectional"))
    )
    (net (code "27") (name "AP4_GP60{slash}TT_~{PG}") (class "Default")
      (node (ref "P3") (pin "P$1") (pinfunction "P$1_P$1") (pintype "bidirectional"))
      (node (ref "P3") (pin "P$2") (pinfunction "P$1_P$2") (pintype "bidirectional"))
      (node (ref "P3") (pin "P$3") (pinfunction "P$1_P$3") (pintype "bidirectional"))
      (node (ref "U1") (pin "K8") (pinfunction "GPIO60_K8") (pintype "bidirectional"))
    )
    (net (code "28") (name "AP4_GP65{slash}TT_9DOF_~{RESET}") (class "Default")
      (node (ref "P45") (pin "P$1") (pinfunction "P$1_P$1") (pintype "bidirectional"))
      (node (ref "P45") (pin "P$2") (pinfunction "P$1_P$2") (pintype "bidirectional"))
      (node (ref "P45") (pin "P$3") (pinfunction "P$1_P$3") (pintype "bidirectional"))
      (node (ref "U1") (pin "A7") (pinfunction "GPIO65_A7") (pintype "bidirectional"))
    )
    (net (code "29") (name "AP4_GP66{slash}TT_QI_TS_CTRL") (class "Default")
      (node (ref "P44") (pin "P$1") (pinfunction "P$1_P$1") (pintype "bidirectional"))
      (node (ref "P44") (pin "P$2") (pinfunction "P$1_P$2") (pintype "bidirectional"))
      (node (ref "P44") (pin "P$3") (pinfunction "P$1_P$3") (pintype "bidirectional"))
      (node (ref "U1") (pin "A8") (pinfunction "GPIO66_A8") (pintype "bidirectional"))
    )
    (net (code "30") (name "AP4_GP69{slash}TT_FLASH_~{CS}") (class "Default")
      (node (ref "P42") (pin "P$1") (pinfunction "P$1_P$1") (pintype "bidirectional"))
      (node (ref "P42") (pin "P$2") (pinfunction "P$1_P$2") (pintype "bidirectional"))
      (node (ref "P42") (pin "P$3") (pinfunction "P$1_P$3") (pintype "bidirectional"))
      (node (ref "U1") (pin "B8") (pinfunction "GPIO69_B8") (pintype "bidirectional"))
    )
    (net (code "31") (name "AP4_GP79{slash}TT_LED2_RED") (class "Default")
      (node (ref "P22") (pin "P$1") (pinfunction "P$1_P$1") (pintype "bidirectional"))
      (node (ref "P22") (pin "P$2") (pinfunction "P$1_P$2") (pintype "bidirectional"))
      (node (ref "P22") (pin "P$3") (pinfunction "P$1_P$3") (pintype "bidirectional"))
      (node (ref "U1") (pin "M11") (pinfunction "GPIO79_M11") (pintype "bidirectional"))
    )
    (net (code "32") (name "AP4_GP88{slash}TT_LED2_YELLOW") (class "Default")
      (node (ref "P32") (pin "P$1") (pinfunction "P$1_P$1") (pintype "bidirectional"))
      (node (ref "P32") (pin "P$2") (pinfunction "P$1_P$2") (pintype "bidirectional"))
      (node (ref "P32") (pin "P$3") (pinfunction "P$1_P$3") (pintype "bidirectional"))
      (node (ref "U1") (pin "F9") (pinfunction "GPIO88_F9") (pintype "bidirectional"))
    )
    (net (code "33") (name "AP4_SWDCLK") (class "Default")
      (node (ref "J1") (pin "4") (pinfunction "SWDCLK_4") (pintype "bidirectional"))
      (node (ref "J1") (pin "B4") (pinfunction "SWDCLK_B4") (pintype "bidirectional"))
      (node (ref "U1") (pin "K3") (pinfunction "GPIO20_K3") (pintype "bidirectional"))
    )
    (net (code "34") (name "AP4_SWDIO") (class "Default")
      (node (ref "J1") (pin "2") (pinfunction "SWDIO_2") (pintype "bidirectional"))
      (node (ref "J1") (pin "B2") (pinfunction "SWDIO_B2") (pintype "bidirectional"))
      (node (ref "U1") (pin "J3") (pinfunction "GPIO21_J3") (pintype "bidirectional"))
    )
    (net (code "35") (name "AP4_SWO") (class "Default")
      (node (ref "J1") (pin "6") (pinfunction "SWO_6") (pintype "bidirectional"))
      (node (ref "J1") (pin "B6") (pinfunction "SWO_B6") (pintype "bidirectional"))
      (node (ref "U1") (pin "L4") (pinfunction "GPIO3_L4") (pintype "bidirectional"))
    )
    (net (code "36") (name "AP4_SWTRACE0") (class "Default")
      (node (ref "J2") (pin "2") (pinfunction "SWDIO_2") (pintype "bidirectional"))
      (node (ref "J2") (pin "B2") (pinfunction "SWDIO_B2") (pintype "bidirectional"))
      (node (ref "U1") (pin "K10") (pinfunction "GPIO80_K10") (pintype "bidirectional"))
    )
    (net (code "37") (name "AP4_SWTRACE1") (class "Default")
      (node (ref "J2") (pin "4") (pinfunction "SWDCLK_4") (pintype "bidirectional"))
      (node (ref "J2") (pin "B4") (pinfunction "SWDCLK_B4") (pintype "bidirectional"))
      (node (ref "U1") (pin "L10") (pinfunction "GPIO81_L10") (pintype "bidirectional"))
    )
    (net (code "38") (name "AP4_SWTRACE2") (class "Default")
      (node (ref "J2") (pin "6") (pinfunction "SWO_6") (pintype "bidirectional"))
      (node (ref "J2") (pin "B6") (pinfunction "SWO_B6") (pintype "bidirectional"))
      (node (ref "U1") (pin "L9") (pinfunction "GPIO82_L9") (pintype "bidirectional"))
    )
    (net (code "39") (name "AP4_SWTRACE3") (class "Default")
      (node (ref "J2") (pin "3") (pinfunction "~{RESET}_3") (pintype "bidirectional"))
      (node (ref "J2") (pin "B3") (pinfunction "~{RESET}_B3") (pintype "bidirectional"))
      (node (ref "U1") (pin "K9") (pinfunction "GPIO83_K9") (pintype "bidirectional"))
    )
    (net (code "40") (name "AP4_SWTRACECLK") (class "Default")
      (node (ref "J2") (pin "1") (pinfunction "VTREF_1") (pintype "bidirectional"))
      (node (ref "J2") (pin "B1") (pinfunction "VTREF_B1") (pintype "bidirectional"))
      (node (ref "U1") (pin "F12") (pinfunction "GPIO38_F12") (pintype "bidirectional"))
    )
    (net (code "41") (name "AP4_USB0_N") (class "Default")
      (node (ref "P21") (pin "P$1") (pinfunction "P$1_P$1") (pintype "bidirectional"))
      (node (ref "P21") (pin "P$2") (pinfunction "P$1_P$2") (pintype "bidirectional"))
      (node (ref "P21") (pin "P$3") (pinfunction "P$1_P$3") (pintype "bidirectional"))
      (node (ref "U1") (pin "M8") (pinfunction "USB0PN_M8") (pintype "bidirectional"))
    )
    (net (code "42") (name "AP4_USB0_P") (class "Default")
      (node (ref "P20") (pin "P$1") (pinfunction "P$1_P$1") (pintype "bidirectional"))
      (node (ref "P20") (pin "P$2") (pinfunction "P$1_P$2") (pintype "bidirectional"))
      (node (ref "P20") (pin "P$3") (pinfunction "P$1_P$3") (pintype "bidirectional"))
      (node (ref "U1") (pin "M7") (pinfunction "USB0PP_M7") (pintype "bidirectional"))
    )
    (net (code "43") (name "AP4_VDDBH") (class "Default")
      (node (ref "C25") (pin "1") (pinfunction "1_1") (pintype "bidirectional"))
      (node (ref "L2") (pin "2") (pinfunction "2_2") (pintype "bidirectional"))
      (node (ref "RZ1") (pin "1") (pinfunction "1_1") (pintype "passive"))
      (node (ref "TP1") (pin "P$1") (pinfunction "TESTPOINT_P$1") (pintype "bidirectional"))
      (node (ref "U1") (pin "G12") (pinfunction "VDDBH--BLE_BUCK_VOUT_G12") (pintype "bidirectional"))
    )
    (net (code "44") (name "AP4_VDDBH_RF") (class "Default")
      (node (ref "C12") (pin "P$1") (pinfunction "1_P$1") (pintype "bidirectional"))
      (node (ref "RZ1") (pin "2") (pinfunction "2_2") (pintype "passive"))
      (node (ref "U1") (pin "J1") (pinfunction "VDDBH_RF--BLE_BUCK_RF_VOUT_J1") (pintype "bidirectional"))
    )
    (net (code "45") (name "AP4_VDDF") (class "Default")
      (node (ref "C19") (pin "P$1") (pinfunction "1_P$1") (pintype "bidirectional"))
      (node (ref "C22") (pin "P$1") (pinfunction "1_P$1") (pintype "bidirectional"))
      (node (ref "TP3") (pin "P$1") (pinfunction "TESTPOINT_P$1") (pintype "bidirectional"))
      (node (ref "U1") (pin "C2") (pinfunction "VDDF-MEM_C2") (pintype "bidirectional"))
    )
    (net (code "46") (name "AP4_VDDMIPI_1P8") (class "Default")
      (node (ref "C14") (pin "P$1") (pinfunction "1_P$1") (pintype "bidirectional"))
      (node (ref "P28") (pin "P$1") (pinfunction "P$1_P$1") (pintype "bidirectional"))
      (node (ref "P28") (pin "P$2") (pinfunction "P$1_P$2") (pintype "bidirectional"))
      (node (ref "P28") (pin "P$3") (pinfunction "P$1_P$3") (pintype "bidirectional"))
      (node (ref "RZ4") (pin "1") (pinfunction "1_1") (pintype "passive"))
      (node (ref "U1") (pin "H10") (pinfunction "VDD18-MIPI_H10") (pintype "bidirectional"))
    )
    (net (code "47") (name "AP4_VDDUSB_0P9") (class "Default")
      (node (ref "C24") (pin "P$1") (pinfunction "1_P$1") (pintype "bidirectional"))
      (node (ref "P26") (pin "P$1") (pinfunction "P$1_P$1") (pintype "bidirectional"))
      (node (ref "P26") (pin "P$2") (pinfunction "P$1_P$2") (pintype "bidirectional"))
      (node (ref "P26") (pin "P$3") (pinfunction "P$1_P$3") (pintype "bidirectional"))
      (node (ref "RZ2") (pin "1") (pinfunction "1_1") (pintype "passive"))
      (node (ref "U1") (pin "L7") (pinfunction "VDDUSB0P9_L7") (pintype "bidirectional"))
    )
    (net (code "48") (name "AP4_VDDUSB_3P3") (class "Default")
      (node (ref "C13") (pin "P$1") (pinfunction "1_P$1") (pintype "bidirectional"))
      (node (ref "P27") (pin "P$1") (pinfunction "P$1_P$1") (pintype "bidirectional"))
      (node (ref "P27") (pin "P$2") (pinfunction "P$1_P$2") (pintype "bidirectional"))
      (node (ref "P27") (pin "P$3") (pinfunction "P$1_P$3") (pintype "bidirectional"))
      (node (ref "RZ3") (pin "1") (pinfunction "1_1") (pintype "passive"))
      (node (ref "U1") (pin "K7") (pinfunction "VDDUSB33_K7") (pintype "bidirectional"))
    )
    (net (code "49") (name "AP4_~{RESET}") (class "Default")
      (node (ref "C4") (pin "1") (pinfunction "1_1") (pintype "passive"))
      (node (ref "D1") (pin "1") (pinfunction "C_1") (pintype "passive"))
      (node (ref "J1") (pin "3") (pinfunction "~{RESET}_3") (pintype "bidirectional"))
      (node (ref "J1") (pin "B3") (pinfunction "~{RESET}_B3") (pintype "bidirectional"))
      (node (ref "P38") (pin "P$1") (pinfunction "P$1_P$1") (pintype "bidirectional"))
      (node (ref "P38") (pin "P$2") (pinfunction "P$1_P$2") (pintype "bidirectional"))
      (node (ref "P38") (pin "P$3") (pinfunction "P$1_P$3") (pintype "bidirectional"))
      (node (ref "SJ1") (pin "2") (pinfunction "2_2") (pintype "passive"))
      (node (ref "U1") (pin "A6") (pinfunction "~{RST}_A6") (pintype "input"))
    )
    (net (code "50") (name "BLE_RFOUT") (class "Default")
      (node (ref "P15") (pin "P$1") (pinfunction "P$1_P$1") (pintype "bidirectional"))
      (node (ref "P15") (pin "P$2") (pinfunction "P$1_P$2") (pintype "bidirectional"))
      (node (ref "P15") (pin "P$3") (pinfunction "P$1_P$3") (pintype "bidirectional"))
      (node (ref "S4") (pin "OUT") (pinfunction "A_OUT") (pintype "bidirectional"))
    )
    (net (code "51") (name "GND") (class "Default")
      (node (ref "C10") (pin "P$2") (pinfunction "2_P$2") (pintype "bidirectional"))
      (node (ref "C11") (pin "P$1") (pinfunction "1_P$1") (pintype "bidirectional"))
      (node (ref "C13") (pin "P$2") (pinfunction "2_P$2") (pintype "bidirectional"))
      (node (ref "C14") (pin "P$2") (pinfunction "2_P$2") (pintype "bidirectional"))
      (node (ref "C15") (pin "P$2") (pinfunction "2_P$2") (pintype "bidirectional"))
      (node (ref "C16") (pin "P$2") (pinfunction "2_P$2") (pintype "bidirectional"))
      (node (ref "C17") (pin "P$2") (pinfunction "2_P$2") (pintype "bidirectional"))
      (node (ref "C18") (pin "P$2") (pinfunction "2_P$2") (pintype "bidirectional"))
      (node (ref "C19") (pin "P$2") (pinfunction "2_P$2") (pintype "bidirectional"))
      (node (ref "C2") (pin "2") (pinfunction "2_2") (pintype "passive"))
      (node (ref "C20") (pin "P$2") (pinfunction "2_P$2") (pintype "bidirectional"))
      (node (ref "C21") (pin "P$2") (pinfunction "2_P$2") (pintype "bidirectional"))
      (node (ref "C23") (pin "P$1") (pinfunction "1_P$1") (pintype "bidirectional"))
      (node (ref "C24") (pin "P$2") (pinfunction "2_P$2") (pintype "bidirectional"))
      (node (ref "C25") (pin "2") (pinfunction "2_2") (pintype "bidirectional"))
      (node (ref "C3") (pin "2") (pinfunction "2_2") (pintype "passive"))
      (node (ref "C4") (pin "2") (pinfunction "2_2") (pintype "passive"))
      (node (ref "C5") (pin "P$2") (pinfunction "2_P$2") (pintype "bidirectional"))
      (node (ref "C6") (pin "P$2") (pinfunction "2_P$2") (pintype "bidirectional"))
      (node (ref "C7") (pin "P$2") (pinfunction "2_P$2") (pintype "bidirectional"))
      (node (ref "C8") (pin "P$2") (pinfunction "2_P$2") (pintype "bidirectional"))
      (node (ref "C9") (pin "P$2") (pinfunction "2_P$2") (pintype "bidirectional"))
      (node (ref "CX1") (pin "2") (pinfunction "2_2") (pintype "passive"))
      (node (ref "CX2") (pin "2") (pinfunction "2_2") (pintype "passive"))
      (node (ref "D1") (pin "2") (pinfunction "A_2") (pintype "passive"))
      (node (ref "J1") (pin "5") (pinfunction "GND_5") (pintype "bidirectional"))
      (node (ref "J1") (pin "B5") (pinfunction "GND_B5") (pintype "bidirectional"))
      (node (ref "J2") (pin "5") (pinfunction "GND_5") (pintype "bidirectional"))
      (node (ref "J2") (pin "B5") (pinfunction "GND_B5") (pintype "bidirectional"))
      (node (ref "P13") (pin "P$1") (pinfunction "P$1_P$1") (pintype "bidirectional"))
      (node (ref "P13") (pin "P$2") (pinfunction "P$1_P$2") (pintype "bidirectional"))
      (node (ref "P13") (pin "P$3") (pinfunction "P$1_P$3") (pintype "bidirectional"))
      (node (ref "P37") (pin "P$1") (pinfunction "P$1_P$1") (pintype "bidirectional"))
      (node (ref "P37") (pin "P$2") (pinfunction "P$1_P$2") (pintype "bidirectional"))
      (node (ref "P37") (pin "P$3") (pinfunction "P$1_P$3") (pintype "bidirectional"))
      (node (ref "RZ2") (pin "2") (pinfunction "2_2") (pintype "passive"))
      (node (ref "RZ3") (pin "2") (pinfunction "2_2") (pintype "passive"))
      (node (ref "RZ4") (pin "2") (pinfunction "2_2") (pintype "passive"))
      (node (ref "SJ1") (pin "1") (pinfunction "1_1") (pintype "passive"))
      (node (ref "U1") (pin "B12") (pinfunction "VSSAUDA_B12") (pintype "bidirectional"))
      (node (ref "U1") (pin "B2") (pinfunction "VSSP-BUCK_REGS_GND_B2") (pintype "bidirectional"))
      (node (ref "U1") (pin "B5") (pinfunction "VSSA-ANALOG_GND_B5") (pintype "bidirectional"))
      (node (ref "U1") (pin "D2") (pinfunction "VSS-DGND_FOR_VDDF_AND_PADS_D2") (pintype "bidirectional"))
      (node (ref "U1") (pin "E12") (pinfunction "VSSAUDD_E12") (pintype "bidirectional"))
      (node (ref "U1") (pin "H1") (pinfunction "VSSB-BLE_UNREG_GND_H1") (pintype "bidirectional"))
      (node (ref "U1") (pin "J10") (pinfunction "VSS18-MIPI_J10") (pintype "bidirectional"))
      (node (ref "U1") (pin "L1") (pinfunction "VSSVCO-BLECORE_GND_FOR_VCO_L1") (pintype "bidirectional"))
      (node (ref "U1") (pin "L2") (pinfunction "VSSS-HVSIMOBUCK_GND_L2") (pintype "bidirectional"))
      (node (ref "U1") (pin "L8") (pinfunction "VSSAUSB_L8") (pintype "bidirectional"))
      (node (ref "VR2") (pin "2") (pinfunction "GND_2") (pintype "bidirectional"))
      (node (ref "VR2") (pin "PAD") (pinfunction "GND_PAD") (pintype "bidirectional"))
      (node (ref "X2") (pin "2") (pinfunction "GND_2") (pintype "bidirectional"))
      (node (ref "X2") (pin "4") (pinfunction "GND_4") (pintype "bidirectional"))
    )
    (net (code "52") (name "Net-(C1-Pad1)") (class "Default")
      (node (ref "C1") (pin "1") (pinfunction "1_1") (pintype "passive"))
      (node (ref "L3") (pin "2") (pinfunction "2_2") (pintype "passive"))
      (node (ref "L4") (pin "1") (pinfunction "1_1") (pintype "passive"))
    )
    (net (code "53") (name "Net-(C6-1)") (class "Default")
      (node (ref "C6") (pin "P$1") (pinfunction "1_P$1") (pintype "bidirectional"))
      (node (ref "RZ6") (pin "1") (pinfunction "1_1") (pintype "passive"))
      (node (ref "VR2") (pin "1") (pinfunction "OUT_1") (pintype "power_in"))
    )
    (net (code "54") (name "Net-(C11-2)") (class "Default")
      (node (ref "C11") (pin "P$2") (pinfunction "2_P$2") (pintype "bidirectional"))
      (node (ref "U1") (pin "A12") (pinfunction "LPADC_VREF_A12") (pintype "bidirectional"))
    )
    (net (code "55") (name "Net-(C16-1)") (class "Default")
      (node (ref "C16") (pin "P$1") (pinfunction "1_P$1") (pintype "bidirectional"))
      (node (ref "U1") (pin "C1") (pinfunction "VDDS-SRAM_HV_SUP_C1") (pintype "bidirectional"))
    )
    (net (code "56") (name "Net-(C17-1)") (class "Default")
      (node (ref "C17") (pin "P$1") (pinfunction "1_P$1") (pintype "bidirectional"))
      (node (ref "U1") (pin "A3") (pinfunction "VDDC-CORE_A3") (pintype "bidirectional"))
    )
    (net (code "57") (name "Net-(C18-1)") (class "Default")
      (node (ref "C18") (pin "P$1") (pinfunction "1_P$1") (pintype "bidirectional"))
      (node (ref "U1") (pin "B3") (pinfunction "VDDC_LV-CORE_LV_B3") (pintype "bidirectional"))
    )
    (net (code "58") (name "Net-(C23-2)") (class "Default")
      (node (ref "C23") (pin "P$2") (pinfunction "2_P$2") (pintype "bidirectional"))
      (node (ref "U1") (pin "B10") (pinfunction "LPMICBIAS_B10") (pintype "output"))
    )
    (net (code "59") (name "Net-(D2-PadC1)") (class "Default")
      (node (ref "D2") (pin "C1") (pinfunction "C1_C1") (pintype "bidirectional"))
      (node (ref "R2") (pin "1") (pinfunction "1_1") (pintype "passive"))
    )
    (net (code "60") (name "Net-(D2-PadC2)") (class "Default")
      (node (ref "D2") (pin "C2") (pinfunction "C2_C2") (pintype "bidirectional"))
      (node (ref "R1") (pin "1") (pinfunction "1_1") (pintype "passive"))
    )
    (net (code "61") (name "Net-(L1-1)") (class "Default")
      (node (ref "L1") (pin "P$1") (pinfunction "1_P$1") (pintype "bidirectional"))
      (node (ref "U1") (pin "A1") (pinfunction "SIMOBUCK_SW_A1") (pintype "bidirectional"))
    )
    (net (code "62") (name "Net-(L1-2)") (class "Default")
      (node (ref "L1") (pin "P$2") (pinfunction "2_P$2") (pintype "bidirectional"))
      (node (ref "U1") (pin "A2") (pinfunction "SIMOBUCK_SWSEL_A2") (pintype "bidirectional"))
    )
    (net (code "63") (name "Net-(L4-Pad2)") (class "Default")
      (node (ref "L4") (pin "2") (pinfunction "2_2") (pintype "passive"))
      (node (ref "S4") (pin "IN") (pinfunction "IN_IN") (pintype "bidirectional"))
    )
    (net (code "64") (name "Net-(U1-RFIOP)") (class "Default")
      (node (ref "CX5") (pin "1") (pinfunction "1_1") (pintype "passive"))
      (node (ref "L3") (pin "1") (pinfunction "1_1") (pintype "passive"))
      (node (ref "U1") (pin "M2") (pinfunction "RFIOP_M2") (pintype "bidirectional"))
    )
    (net (code "65") (name "Net-(U1-VDDBH_SW--BLE_BUCK_SW)") (class "Default")
      (node (ref "L2") (pin "1") (pinfunction "1_1") (pintype "bidirectional"))
      (node (ref "U1") (pin "H12") (pinfunction "VDDBH_SW--BLE_BUCK_SW_H12") (pintype "bidirectional"))
    )
    (net (code "66") (name "Net-(U1-XI)") (class "Default")
      (node (ref "C3") (pin "1") (pinfunction "1_1") (pintype "passive"))
      (node (ref "U1") (pin "A4") (pinfunction "XI_A4") (pintype "bidirectional"))
      (node (ref "X1") (pin "2") (pinfunction "2_2") (pintype "bidirectional"))
    )
    (net (code "67") (name "Net-(U1-XI32M)") (class "Default")
      (node (ref "CX2") (pin "1") (pinfunction "1_1") (pintype "passive"))
      (node (ref "U1") (pin "C12") (pinfunction "XI32M_C12") (pintype "bidirectional"))
      (node (ref "X2") (pin "3") (pinfunction "2_3") (pintype "bidirectional"))
    )
    (net (code "68") (name "Net-(U1-XO)") (class "Default")
      (node (ref "C2") (pin "1") (pinfunction "1_1") (pintype "passive"))
      (node (ref "U1") (pin "A5") (pinfunction "XO_A5") (pintype "bidirectional"))
      (node (ref "X1") (pin "1") (pinfunction "1_1") (pintype "bidirectional"))
    )
    (net (code "69") (name "Net-(U1-XO32M)") (class "Default")
      (node (ref "CX1") (pin "1") (pinfunction "1_1") (pintype "passive"))
      (node (ref "U1") (pin "D12") (pinfunction "XO32M_D12") (pintype "bidirectional"))
      (node (ref "X2") (pin "1") (pinfunction "1_1") (pintype "bidirectional"))
    )
    (net (code "70") (name "Net-(VR2-EN)") (class "Default")
      (node (ref "RZ5") (pin "2") (pinfunction "2_2") (pintype "passive"))
      (node (ref "VR2") (pin "3") (pinfunction "EN_3") (pintype "input"))
    )
    (net (code "71") (name "P18_UNUSED") (class "Default")
      (node (ref "P18") (pin "P$1") (pinfunction "P$1_P$1") (pintype "bidirectional"))
      (node (ref "P18") (pin "P$2") (pinfunction "P$1_P$2") (pintype "bidirectional"))
      (node (ref "P18") (pin "P$3") (pinfunction "P$1_P$3") (pintype "bidirectional"))
    )
    (net (code "72") (name "P19_UNUSED") (class "Default")
      (node (ref "P19") (pin "P$1") (pinfunction "P$1_P$1") (pintype "bidirectional"))
      (node (ref "P19") (pin "P$2") (pinfunction "P$1_P$2") (pintype "bidirectional"))
      (node (ref "P19") (pin "P$3") (pinfunction "P$1_P$3") (pintype "bidirectional"))
    )
    (net (code "73") (name "P25_UNUSED") (class "Default")
      (node (ref "P25") (pin "P$1") (pinfunction "P$1_P$1") (pintype "bidirectional"))
      (node (ref "P25") (pin "P$2") (pinfunction "P$1_P$2") (pintype "bidirectional"))
      (node (ref "P25") (pin "P$3") (pinfunction "P$1_P$3") (pintype "bidirectional"))
    )
    (net (code "74") (name "P39_UNUSED") (class "Default")
      (node (ref "P39") (pin "P$1") (pinfunction "P$1_P$1") (pintype "bidirectional"))
      (node (ref "P39") (pin "P$2") (pinfunction "P$1_P$2") (pintype "bidirectional"))
      (node (ref "P39") (pin "P$3") (pinfunction "P$1_P$3") (pintype "bidirectional"))
    )
    (net (code "75") (name "VDD") (class "Default")
      (node (ref "C5") (pin "P$1") (pinfunction "1_P$1") (pintype "bidirectional"))
      (node (ref "P29") (pin "P$1") (pinfunction "P$1_P$1") (pintype "bidirectional"))
      (node (ref "P29") (pin "P$2") (pinfunction "P$1_P$2") (pintype "bidirectional"))
      (node (ref "P29") (pin "P$3") (pinfunction "P$1_P$3") (pintype "bidirectional"))
      (node (ref "RZ5") (pin "1") (pinfunction "1_1") (pintype "passive"))
      (node (ref "VR2") (pin "4") (pinfunction "IN_4") (pintype "bidirectional"))
    )
    (net (code "76") (name "VDDAUDA_1P8-CLEAN") (class "Default")
      (node (ref "C15") (pin "P$1") (pinfunction "1_P$1") (pintype "bidirectional"))
      (node (ref "RZ6") (pin "2") (pinfunction "2_2") (pintype "passive"))
      (node (ref "U1") (pin "B11") (pinfunction "VDDAUDA_B11") (pintype "bidirectional"))
    )
    (net (code "77") (name "unconnected-(U1-GPIO0-PadH3)") (class "Default")
      (node (ref "U1") (pin "H3") (pinfunction "GPIO0_H3") (pintype "bidirectional"))
    )
    (net (code "78") (name "unconnected-(U1-GPIO1-PadJ4)") (class "Default")
      (node (ref "U1") (pin "J4") (pinfunction "GPIO1_J4") (pintype "bidirectional"))
    )
    (net (code "79") (name "unconnected-(U1-GPIO2-PadK4)") (class "Default")
      (node (ref "U1") (pin "K4") (pinfunction "GPIO2_K4") (pintype "bidirectional"))
    )
    (net (code "80") (name "unconnected-(U1-GPIO4-PadM4)") (class "Default")
      (node (ref "U1") (pin "M4") (pinfunction "GPIO4_M4") (pintype "bidirectional"))
    )
    (net (code "81") (name "unconnected-(U1-GPIO5-PadH4)") (class "Default")
      (node (ref "U1") (pin "H4") (pinfunction "GPIO5_H4") (pintype "bidirectional"))
    )
    (net (code "82") (name "unconnected-(U1-GPIO7-PadJ6)") (class "Default")
      (node (ref "U1") (pin "J6") (pinfunction "GPIO7_J6") (pintype "bidirectional"))
    )
    (net (code "83") (name "unconnected-(U1-GPIO10-PadE6)") (class "Default")
      (node (ref "U1") (pin "E6") (pinfunction "GPIO10_E6") (pintype "bidirectional"))
    )
    (net (code "84") (name "unconnected-(U1-GPIO11-PadE4)") (class "Default")
      (node (ref "U1") (pin "E4") (pinfunction "GPIO11_E4") (pintype "bidirectional"))
    )
    (net (code "85") (name "unconnected-(U1-GPIO12-PadB4)") (class "Default")
      (node (ref "U1") (pin "B4") (pinfunction "GPIO12_B4") (pintype "bidirectional"))
    )
    (net (code "86") (name "unconnected-(U1-GPIO15-PadE5)") (class "Default")
      (node (ref "U1") (pin "E5") (pinfunction "GPIO15_E5") (pintype "bidirectional"))
    )
    (net (code "87") (name "unconnected-(U1-GPIO16-PadD7)") (class "Default")
      (node (ref "U1") (pin "D7") (pinfunction "GPIO16_D7") (pintype "bidirectional"))
    )
    (net (code "88") (name "unconnected-(U1-GPIO19-PadC3)") (class "Default")
      (node (ref "U1") (pin "C3") (pinfunction "GPIO19_C3") (pintype "bidirectional"))
    )
    (net (code "89") (name "unconnected-(U1-GPIO22-PadF3)") (class "Default")
      (node (ref "U1") (pin "F3") (pinfunction "GPIO22_F3") (pintype "bidirectional"))
    )
    (net (code "90") (name "unconnected-(U1-GPIO23-PadF2)") (class "Default")
      (node (ref "U1") (pin "F2") (pinfunction "GPIO23_F2") (pintype "bidirectional"))
    )
    (net (code "91") (name "unconnected-(U1-GPIO28-PadE3)") (class "Default")
      (node (ref "U1") (pin "E3") (pinfunction "GPIO28_E3") (pintype "bidirectional"))
    )
    (net (code "92") (name "unconnected-(U1-GPIO37-PadF11)") (class "Default")
      (node (ref "U1") (pin "F11") (pinfunction "GPIO37_F11") (pintype "bidirectional"))
    )
    (net (code "93") (name "unconnected-(U1-GPIO52-PadC10)") (class "Default")
      (node (ref "U1") (pin "C10") (pinfunction "GPIO52_C10") (pintype "bidirectional"))
    )
    (net (code "94") (name "unconnected-(U1-GPIO54-PadD10)") (class "Default")
      (node (ref "U1") (pin "D10") (pinfunction "GPIO54_D10") (pintype "bidirectional"))
    )
    (net (code "95") (name "unconnected-(U1-GPIO56-PadE10)") (class "Default")
      (node (ref "U1") (pin "E10") (pinfunction "GPIO56_E10") (pintype "bidirectional"))
    )
    (net (code "96") (name "unconnected-(U1-GPIO57-PadE9)") (class "Default")
      (node (ref "U1") (pin "E9") (pinfunction "GPIO57_E9") (pintype "bidirectional"))
    )
    (net (code "97") (name "unconnected-(U1-GPIO59-PadJ8)") (class "Default")
      (node (ref "U1") (pin "J8") (pinfunction "GPIO59_J8") (pintype "bidirectional"))
    )
    (net (code "98") (name "unconnected-(U1-GPIO61-PadK6)") (class "Default")
      (node (ref "U1") (pin "K6") (pinfunction "GPIO61_K6") (pintype "bidirectional"))
    )
    (net (code "99") (name "unconnected-(U1-GPIO62-PadL6)") (class "Default")
      (node (ref "U1") (pin "L6") (pinfunction "GPIO62_L6") (pintype "bidirectional"))
    )
    (net (code "100") (name "unconnected-(U1-GPIO63-PadM6)") (class "Default")
      (node (ref "U1") (pin "M6") (pinfunction "GPIO63_M6") (pintype "bidirectional"))
    )
    (net (code "101") (name "unconnected-(U1-GPIO64-PadB6)") (class "Default")
      (node (ref "U1") (pin "B6") (pinfunction "GPIO64_B6") (pintype "bidirectional"))
    )
    (net (code "102") (name "unconnected-(U1-GPIO67-PadC6)") (class "Default")
      (node (ref "U1") (pin "C6") (pinfunction "GPIO67_C6") (pintype "bidirectional"))
    )
    (net (code "103") (name "unconnected-(U1-GPIO68-PadB7)") (class "Default")
      (node (ref "U1") (pin "B7") (pinfunction "GPIO68_B7") (pintype "bidirectional"))
    )
    (net (code "104") (name "unconnected-(U1-GPIO70-PadC5)") (class "Default")
      (node (ref "U1") (pin "C5") (pinfunction "GPIO70_C5") (pintype "bidirectional"))
    )
    (net (code "105") (name "unconnected-(U1-GPIO71-PadC7)") (class "Default")
      (node (ref "U1") (pin "C7") (pinfunction "GPIO71_C7") (pintype "bidirectional"))
    )
    (net (code "106") (name "unconnected-(U1-GPIO72-PadC8)") (class "Default")
      (node (ref "U1") (pin "C8") (pinfunction "GPIO72_C8") (pintype "bidirectional"))
    )
    (net (code "107") (name "unconnected-(U1-GPIO73-PadD8)") (class "Default")
      (node (ref "U1") (pin "D8") (pinfunction "GPIO73_D8") (pintype "bidirectional"))
    )
    (net (code "108") (name "unconnected-(U1-GPIO74-PadG11)") (class "Default")
      (node (ref "U1") (pin "G11") (pinfunction "GPIO74_G11") (pintype "bidirectional"))
    )
    (net (code "109") (name "unconnected-(U1-GPIO75-PadH11)") (class "Default")
      (node (ref "U1") (pin "H11") (pinfunction "GPIO75_H11") (pintype "bidirectional"))
    )
    (net (code "110") (name "unconnected-(U1-GPIO76-PadJ11)") (class "Default")
      (node (ref "U1") (pin "J11") (pinfunction "GPIO76_J11") (pintype "bidirectional"))
    )
    (net (code "111") (name "unconnected-(U1-GPIO77-PadK11)") (class "Default")
      (node (ref "U1") (pin "K11") (pinfunction "GPIO77_K11") (pintype "bidirectional"))
    )
    (net (code "112") (name "unconnected-(U1-GPIO78-PadL11)") (class "Default")
      (node (ref "U1") (pin "L11") (pinfunction "GPIO78_L11") (pintype "bidirectional"))
    )
    (net (code "113") (name "unconnected-(U1-GPIO84-PadJ9)") (class "Default")
      (node (ref "U1") (pin "J9") (pinfunction "GPIO84_J9") (pintype "bidirectional"))
    )
    (net (code "114") (name "unconnected-(U1-GPIO85-PadH9)") (class "Default")
      (node (ref "U1") (pin "H9") (pinfunction "GPIO85_H9") (pintype "bidirectional"))
    )
    (net (code "115") (name "unconnected-(U1-GPIO86-PadG10)") (class "Default")
      (node (ref "U1") (pin "G10") (pinfunction "GPIO86_G10") (pintype "bidirectional"))
    )
    (net (code "116") (name "unconnected-(U1-GPIO87-PadG9)") (class "Default")
      (node (ref "U1") (pin "G9") (pinfunction "GPIO87_G9") (pintype "bidirectional"))
    )
    (net (code "117") (name "unconnected-(U1-GPIO89-PadF10)") (class "Default")
      (node (ref "U1") (pin "F10") (pinfunction "GPIO89_F10") (pintype "bidirectional"))
    )
    (net (code "118") (name "unconnected-(U1-GPIO90-PadJ2)") (class "Default")
      (node (ref "U1") (pin "J2") (pinfunction "GPIO90_J2") (pintype "bidirectional"))
    )
    (net (code "119") (name "unconnected-(U1-GPIO91-PadK2)") (class "Default")
      (node (ref "U1") (pin "K2") (pinfunction "GPIO91_K2") (pintype "bidirectional"))
    )
    (net (code "120") (name "unconnected-(U1-LPADC_D0NSE0-PadA10)") (class "Default")
      (node (ref "U1") (pin "A10") (pinfunction "LPADC_D0NSE0_A10") (pintype "input"))
    )
    (net (code "121") (name "unconnected-(U1-LPADC_D0PSE1-PadA11)") (class "Default")
      (node (ref "U1") (pin "A11") (pinfunction "LPADC_D0PSE1_A11") (pintype "input"))
    )
    (net (code "122") (name "unconnected-(U1-LPADC_D1NSE2-PadC11)") (class "Default")
      (node (ref "U1") (pin "C11") (pinfunction "LPADC_D1NSE2_C11") (pintype "input"))
    )
    (net (code "123") (name "unconnected-(U1-LPADC_D1PSE3-PadD11)") (class "Default")
      (node (ref "U1") (pin "D11") (pinfunction "LPADC_D1PSE3_D11") (pintype "input"))
    )
    (net (code "124") (name "unconnected-(U1-MIPI_CLKN-PadJ12)") (class "Default")
      (node (ref "U1") (pin "J12") (pinfunction "MIPI_CLKN_J12") (pintype "bidirectional"))
    )
    (net (code "125") (name "unconnected-(U1-MIPI_CLKP-PadK12)") (class "Default")
      (node (ref "U1") (pin "K12") (pinfunction "MIPI_CLKP_K12") (pintype "bidirectional"))
    )
    (net (code "126") (name "unconnected-(U1-MIPI_DON-PadL12)") (class "Default")
      (node (ref "U1") (pin "L12") (pinfunction "MIPI_DON_L12") (pintype "bidirectional"))
    )
    (net (code "127") (name "unconnected-(U1-MIPI_DOP-PadM12)") (class "Default")
      (node (ref "U1") (pin "M12") (pinfunction "MIPI_DOP_M12") (pintype "bidirectional"))
    )
    (net (code "128") (name "unconnected-(U1-TXEN-PadK1)") (class "Default")
      (node (ref "U1") (pin "K1") (pinfunction "TXEN_K1") (pintype "output"))
    )
  )
)
